# openSX70_ALPHA_V8-20181105-MLF32.net
KiCad netlist of a schematic drawn in EAGLE
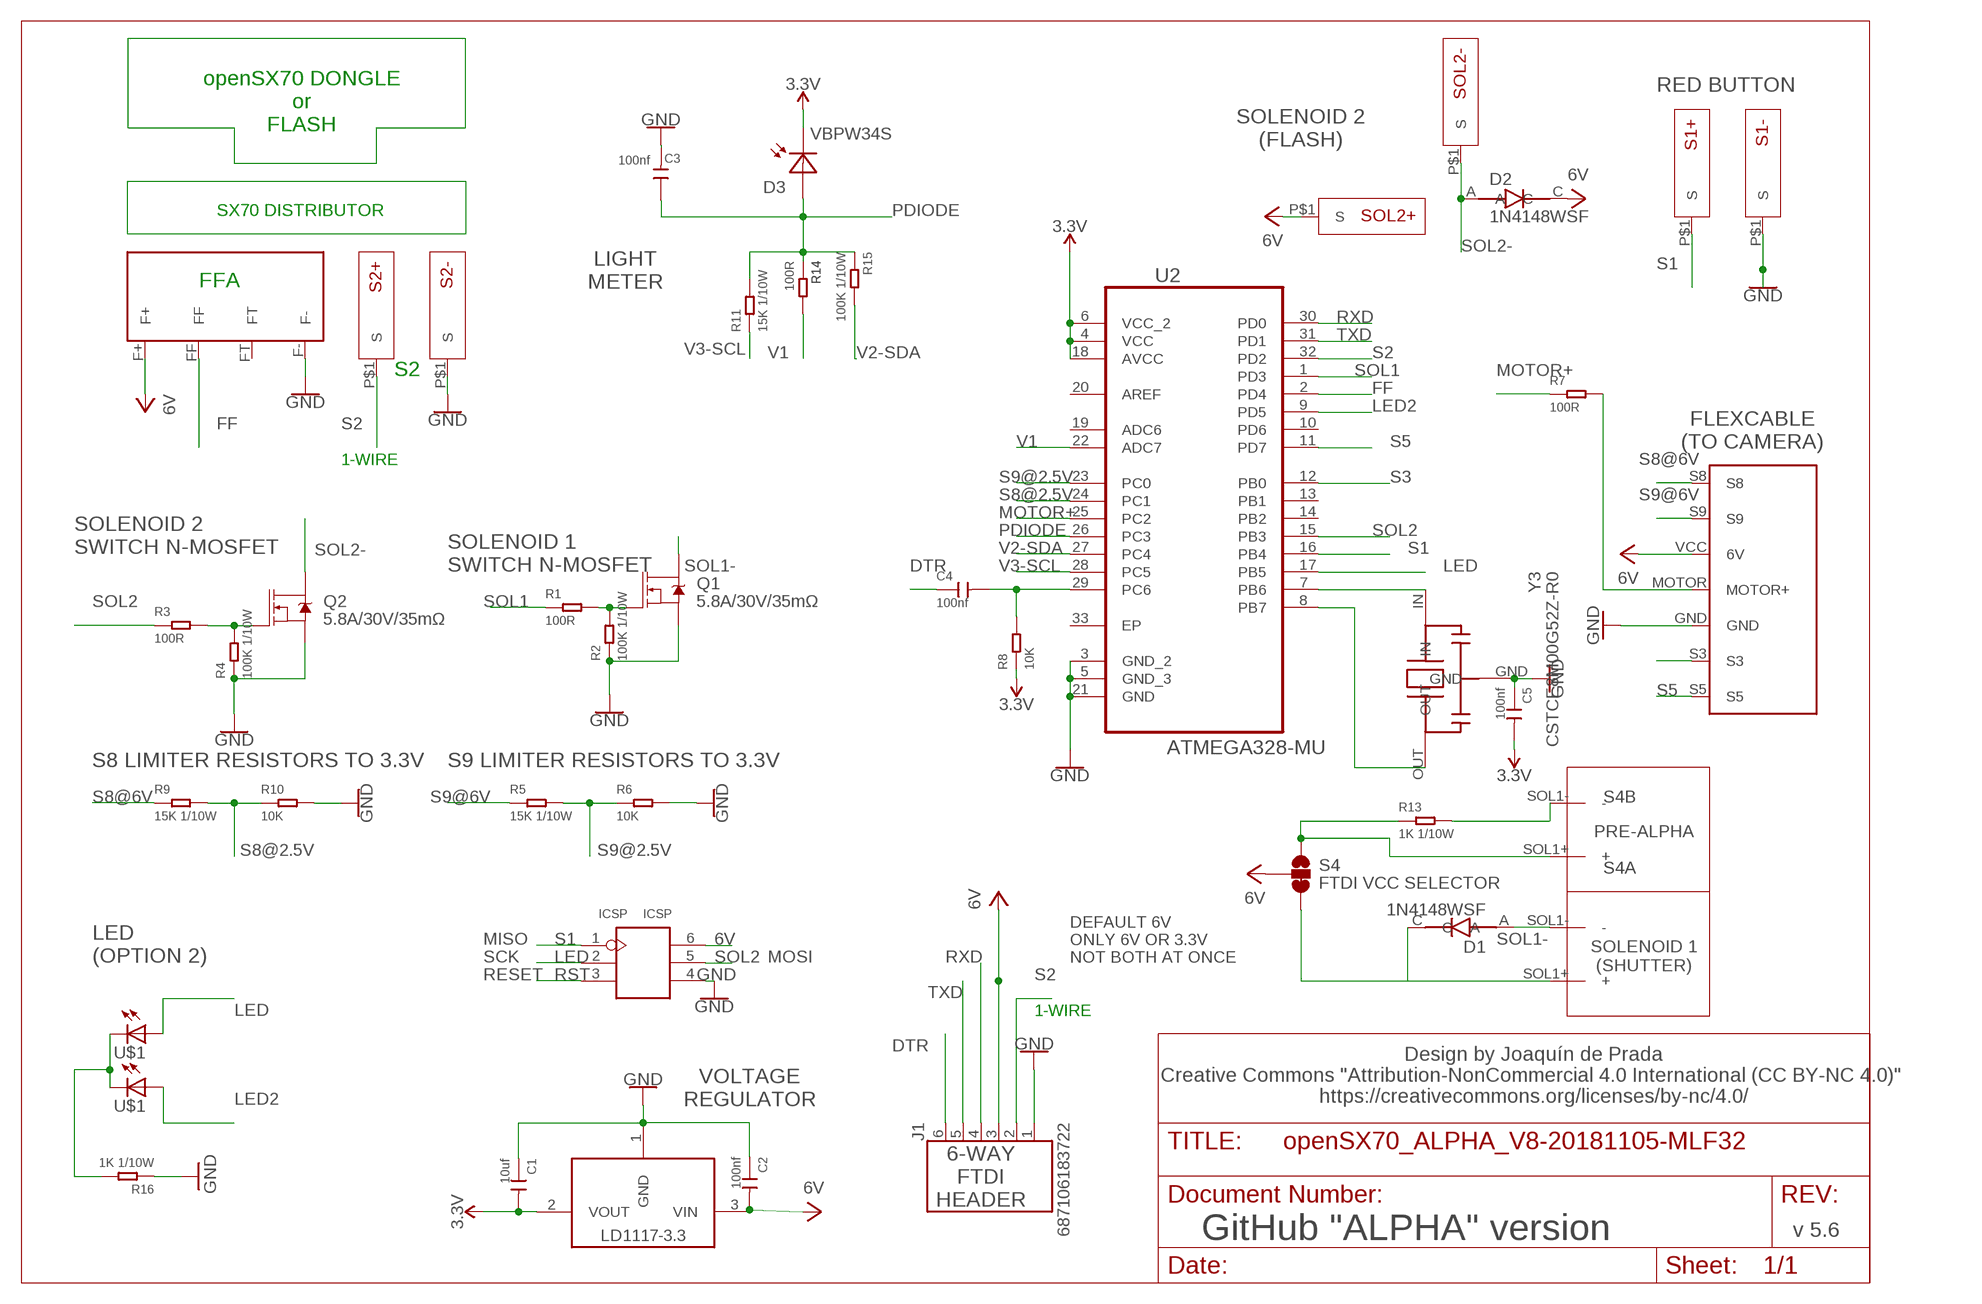
[diagram p0: schematic, sheet 1]

(export (version "E")
  (design (tool "Eeschema 10.0.6"))
  (components
    (comp (ref "C1")
      (value "10uf")
      (footprint "eagle-import:C0603")
      (fields (field (name "MPN") "CC0603KRX5R6BB106"))
      (libsource (lib "eagle-import") (part "CERAMIC-10UF-10V-10%-X5R(0603)"))
    )
    (comp (ref "C2")
      (value "100nf")
      (footprint "eagle-import:C0603")
      (fields (field (name "MPN") "CC0603KRX7R9BB104"))
      (libsource (lib "eagle-import") (part "CERAMIC-100NF-50V-10%-X7R(0603)"))
    )
    (comp (ref "C3")
      (value "100nf")
      (footprint "eagle-import:C0603")
      (fields (field (name "MPN") "CC0603KRX7R9BB104"))
      (libsource (lib "eagle-import") (part "CERAMIC-100NF-50V-10%-X7R(0603)"))
    )
    (comp (ref "C4")
      (value "100nf")
      (footprint "eagle-import:C0603")
      (fields (field (name "MPN") "CC0603KRX7R9BB104"))
      (libsource (lib "eagle-import") (part "CERAMIC-100NF-50V-10%-X7R(0603)"))
    )
    (comp (ref "C5")
      (value "100nf")
      (footprint "eagle-import:C0603")
      (fields (field (name "MPN") "CC0603KRX7R9BB104"))
      (libsource (lib "eagle-import") (part "CERAMIC-100NF-50V-10%-X7R(0603)"))
    )
    (comp (ref "D1")
      (value "1N4148WSF")
      (footprint "eagle-import:SODFL2512X100N")
      (fields (field (name "MANUFACTURER") "Fairchild Semiconductor"))
      (libsource (lib "eagle-import") (part "1N4148WS"))
    )
    (comp (ref "D2")
      (value "1N4148WSF")
      (footprint "eagle-import:SODFL2512X100N")
      (fields (field (name "MANUFACTURER") "Fairchild Semiconductor"))
      (libsource (lib "eagle-import") (part "1N4148WS"))
    )
    (comp (ref "D3")
      (value "VBPW34S")
      (footprint "eagle-import:SOD6439X130N")
      (fields (field (name "DIGI-KEY_PART_NUMBER") "751-1500-1-ND") (field (name "MF") "Vishay"))
      (libsource (lib "eagle-import") (part "VBPW34S"))
    )
    (comp (ref "ICSP")
      (value "ICSP")
      (footprint "eagle-import:H2X3-2.54")
      (libsource (lib "eagle-import") (part "ICSP"))
    )
    (comp (ref "J1")
      (value "687106183722")
      (footprint "eagle-import:687106183722")
      (fields (field (name "MF") "Wurth Electronics"))
      (libsource (lib "eagle-import") (part "687106183722"))
    )
    (comp (ref "LD11172.5V")
      (value "LD1117 2.5V")
      (footprint "eagle-import:SOT223")
      (fields (field (name "MF") "Advanced Monolithic Systems") (field (name "MP") "AMS1117-5.0"))
      (libsource (lib "eagle-import") (part "LD1117-3.3"))
    )
    (comp (ref "Q1")
      (value "5.8A/30V/35mΩ")
      (footprint "eagle-import:SOT23-3")
      (libsource (lib "eagle-import") (part "MOSFET-NCH-AO3404A"))
    )
    (comp (ref "Q2")
      (value "5.8A/30V/35mΩ")
      (footprint "eagle-import:SOT23-3")
      (libsource (lib "eagle-import") (part "MOSFET-NCH-AO3404A"))
    )
    (comp (ref "R1")
      (value "100R")
      (footprint "eagle-import:R0603")
      (fields (field (name "MPN") "RC0603JR-07100RL"))
      (libsource (lib "eagle-import") (part "SMD-RES-100R-5%-1/10W(0603)"))
    )
    (comp (ref "R2")
      (value "100K 1/10W")
      (footprint "eagle-import:R0603")
      (fields (field (name "MPN") "RC0603JR-07100KL"))
      (libsource (lib "eagle-import") (part "SMD-RES-100K-5%-1/10W(0603)"))
    )
    (comp (ref "R3")
      (value "100R")
      (footprint "eagle-import:R0603")
      (fields (field (name "MPN") "RC0603JR-07100RL"))
      (libsource (lib "eagle-import") (part "SMD-RES-100R-5%-1/10W(0603)"))
    )
    (comp (ref "R4")
      (value "100K 1/10W")
      (footprint "eagle-import:R0603")
      (fields (field (name "MPN") "RC0603JR-07100KL"))
      (libsource (lib "eagle-import") (part "SMD-RES-100K-5%-1/10W(0603)"))
    )
    (comp (ref "R5")
      (value "15K 1/10W")
      (footprint "eagle-import:R0603")
      (fields (field (name "MPN") "RC0603FR-0715KL"))
      (libsource (lib "eagle-import") (part "SMD-RES-15K-1%-1/10W(0603)"))
    )
    (comp (ref "R6")
      (value "10K")
      (footprint "eagle-import:R0603")
      (fields (field (name "MPN") "RC0603FR-0710KL"))
      (libsource (lib "eagle-import") (part "SMD-RES-10K-1%-1/10W(0603)"))
    )
    (comp (ref "R7")
      (value "100R")
      (footprint "eagle-import:R0603")
      (fields (field (name "MPN") "RC0603JR-07100RL"))
      (libsource (lib "eagle-import") (part "SMD-RES-100R-5%-1/10W(0603)"))
    )
    (comp (ref "R8")
      (value "10K")
      (footprint "eagle-import:R0603")
      (fields (field (name "MPN") "RC0603FR-0710KL"))
      (libsource (lib "eagle-import") (part "SMD-RES-10K-1%-1/10W(0603)"))
    )
    (comp (ref "R9")
      (value "15K 1/10W")
      (footprint "eagle-import:R0603")
      (fields (field (name "MPN") "RC0603FR-0715KL"))
      (libsource (lib "eagle-import") (part "SMD-RES-15K-1%-1/10W(0603)"))
    )
    (comp (ref "R10")
      (value "10K")
      (footprint "eagle-import:R0603")
      (fields (field (name "MPN") "RC0603FR-0710KL"))
      (libsource (lib "eagle-import") (part "SMD-RES-10K-1%-1/10W(0603)"))
    )
    (comp (ref "R11")
      (value "15K 1/10W")
      (footprint "eagle-import:R0603")
      (fields (field (name "MPN") "RC0603FR-0715KL"))
      (libsource (lib "eagle-import") (part "SMD-RES-15K-1%-1/10W(0603)"))
    )
    (comp (ref "R13")
      (value "1K 1/10W")
      (footprint "eagle-import:R0603")
      (fields (field (name "MPN") "RC0603JR-071KL"))
      (libsource (lib "eagle-import") (part "SMD-RES-1K-5%-1/10W(0603)"))
    )
    (comp (ref "R14")
      (value "100R")
      (footprint "eagle-import:R0603")
      (fields (field (name "MPN") "RC0603JR-07100RL"))
      (libsource (lib "eagle-import") (part "SMD-RES-100R-5%-1/10W(0603)"))
    )
    (comp (ref "R15")
      (value "100K 1/10W")
      (footprint "eagle-import:R0603")
      (fields (field (name "MPN") "RC0603JR-07100KL"))
      (libsource (lib "eagle-import") (part "SMD-RES-100K-5%-1/10W(0603)"))
    )
    (comp (ref "R16")
      (value "1K 1/10W")
      (footprint "eagle-import:R0603")
      (fields (field (name "MPN") "RC0603JR-071KL"))
      (libsource (lib "eagle-import") (part "SMD-RES-1K-5%-1/10W(0603)"))
    )
    (comp (ref "S1+")
      (value "SX70-S-PAD-NEW")
      (footprint "eagle-import:SX70-S-PAD2")
      (libsource (lib "eagle-import") (part "SX70-S-PAD-NEW"))
    )
    (comp (ref "S1-")
      (value "SX70-S-PAD-NEW")
      (footprint "eagle-import:SX70-S-PAD2")
      (libsource (lib "eagle-import") (part "SX70-S-PAD-NEW"))
    )
    (comp (ref "S2+")
      (value "SX70-S-PAD-NEW")
      (footprint "eagle-import:SX70-S-PAD2")
      (libsource (lib "eagle-import") (part "SX70-S-PAD-NEW"))
    )
    (comp (ref "S2-")
      (value "SX70-S-PAD-NEW")
      (footprint "eagle-import:SX70-S-PAD2")
      (libsource (lib "eagle-import") (part "SX70-S-PAD-NEW"))
    )
    (comp (ref "S4")
      (value "FTDI VCC SELECTOR")
      (footprint "eagle-import:SMT-JUMPER_3_1-NC_TRACE_SILK")
      (libsource (lib "eagle-import") (part "JUMPER-SMT_3_1-NC_TRACE_SILK"))
    )
    (comp (ref "SOL1")
      (value "SX70-SOLENOID1-2PADS")
      (footprint "eagle-import:SX70-SOLENOID1-2")
      (libsource (lib "eagle-import") (part "SX70-SOLENOID1-2PADS"))
    )
    (comp (ref "SOL2")
      (value "SX70-SOLENOID1-2PADS")
      (footprint "eagle-import:SX70-SOLENOID1-2")
      (libsource (lib "eagle-import") (part "SX70-SOLENOID1-2PADS"))
    )
    (comp (ref "SOL2+")
      (value "SX70-S-PAD-NEW")
      (footprint "eagle-import:SX70-S-PAD2")
      (libsource (lib "eagle-import") (part "SX70-S-PAD-NEW"))
    )
    (comp (ref "SOL2-")
      (value "SX70-S-PAD-NEW")
      (footprint "eagle-import:SX70-S-PAD2")
      (libsource (lib "eagle-import") (part "SX70-S-PAD-NEW"))
    )
    (comp (ref "U$1")
      (value "DUAL-LED-0603-BIS")
      (footprint "eagle-import:LED_APHB1608SYKSURKC")
      (libsource (lib "eagle-import") (part "DUAL-LED-0603-BIS"))
    )
    (comp (ref "U$2")
      (value "FFA")
      (footprint "eagle-import:FFA-PAD-PACKAGE")
      (libsource (lib "eagle-import") (part "SX70-FFA-PAD"))
    )
    (comp (ref "U$3")
      (value "SX70-7-PAD")
      (footprint "eagle-import:SX70-7-PAD-PROPER")
      (libsource (lib "eagle-import") (part "SX70-7-PAD"))
    )
    (comp (ref "U2")
      (value "ATMEGA328-MU")
      (footprint "eagle-import:QFN50P500X500X100-33N")
      (fields (field (name "MF") "Microchip"))
      (libsource (lib "eagle-import") (part "ATMEGA328-MU"))
    )
    (comp (ref "Y3")
      (value "CSTCE8M00G52Z-R0")
      (footprint "eagle-import:CFP95P160X100-3N")
      (fields (field (name "MF") "Murata") (field (name "MP") "CSTCE16M0V53-R0"))
      (libsource (lib "eagle-import") (part "CSTCE16M0V53-R0"))
    )
  )
  (nets
    (net (code "1") (name "/DTR") (class "Default")
      (node (ref "C4") (pin "1") (pinfunction "1_1") (pintype "passive"))
      (node (ref "J1") (pin "6") (pinfunction "1_6") (pintype "passive"))
    )
    (net (code "2") (name "/FF") (class "Default")
      (node (ref "U$2") (pin "FF") (pinfunction "FF_FF") (pintype "bidirectional"))
      (node (ref "U2") (pin "2") (pinfunction "PD4_2") (pintype "bidirectional"))
    )
    (net (code "3") (name "/LED") (class "Default")
      (node (ref "ICSP") (pin "2") (pinfunction "SCK_2") (pintype "bidirectional"))
      (node (ref "U$1") (pin "1") (pinfunction "A_1") (pintype "passive"))
      (node (ref "U2") (pin "17") (pinfunction "PB5_17") (pintype "bidirectional"))
    )
    (net (code "4") (name "/LED2") (class "Default")
      (node (ref "U$1") (pin "3") (pinfunction "A1_3") (pintype "passive"))
      (node (ref "U2") (pin "9") (pinfunction "PD5_9") (pintype "bidirectional"))
    )
    (net (code "5") (name "/MOTOR+") (class "Default")
      (node (ref "R7") (pin "1") (pinfunction "1_1") (pintype "passive"))
      (node (ref "U2") (pin "25") (pinfunction "PC2_25") (pintype "bidirectional"))
    )
    (net (code "6") (name "/PDIODE") (class "Default")
      (node (ref "C3") (pin "1") (pinfunction "1_1") (pintype "passive"))
      (node (ref "D3") (pin "A") (pinfunction "A_A") (pintype "passive"))
      (node (ref "R11") (pin "2") (pinfunction "2_2") (pintype "passive"))
      (node (ref "R14") (pin "1") (pinfunction "1_1") (pintype "passive"))
      (node (ref "R15") (pin "1") (pinfunction "1_1") (pintype "passive"))
      (node (ref "U2") (pin "26") (pinfunction "PC3_26") (pintype "bidirectional"))
    )
    (net (code "7") (name "/RST") (class "Default")
      (node (ref "ICSP") (pin "3") (pinfunction "RST_3") (pintype "bidirectional"))
    )
    (net (code "8") (name "/RXD") (class "Default")
      (node (ref "J1") (pin "4") (pinfunction "3_4") (pintype "passive"))
      (node (ref "U2") (pin "30") (pinfunction "PD0_30") (pintype "bidirectional"))
    )
    (net (code "9") (name "/S1") (class "Default")
      (node (ref "ICSP") (pin "1") (pinfunction "MISO_1") (pintype "bidirectional"))
      (node (ref "S1+") (pin "P$1") (pinfunction "S_P$1") (pintype "bidirectional"))
      (node (ref "U2") (pin "16") (pinfunction "PB4_16") (pintype "bidirectional"))
    )
    (net (code "10") (name "/S2") (class "Default")
      (node (ref "J1") (pin "2") (pinfunction "5_2") (pintype "passive"))
      (node (ref "S2+") (pin "P$1") (pinfunction "S_P$1") (pintype "bidirectional"))
      (node (ref "U2") (pin "32") (pinfunction "PD2_32") (pintype "bidirectional"))
    )
    (net (code "11") (name "/S3") (class "Default")
      (node (ref "U$3") (pin "S3") (pinfunction "S3_S3") (pintype "bidirectional"))
      (node (ref "U2") (pin "12") (pinfunction "PB0_12") (pintype "bidirectional"))
    )
    (net (code "12") (name "/S5") (class "Default")
      (node (ref "U$3") (pin "S5") (pinfunction "S5_S5") (pintype "bidirectional"))
      (node (ref "U2") (pin "11") (pinfunction "PD7_11") (pintype "bidirectional"))
    )
    (net (code "13") (name "/S8@2.5V") (class "Default")
      (node (ref "R10") (pin "1") (pinfunction "1_1") (pintype "passive"))
      (node (ref "R9") (pin "2") (pinfunction "2_2") (pintype "passive"))
      (node (ref "U2") (pin "24") (pinfunction "PC1_24") (pintype "bidirectional"))
    )
    (net (code "14") (name "/S8@6V") (class "Default")
      (node (ref "R9") (pin "1") (pinfunction "1_1") (pintype "passive"))
      (node (ref "U$3") (pin "S8") (pinfunction "S8_S8") (pintype "bidirectional"))
    )
    (net (code "15") (name "/S9@2.5V") (class "Default")
      (node (ref "R5") (pin "2") (pinfunction "2_2") (pintype "passive"))
      (node (ref "R6") (pin "1") (pinfunction "1_1") (pintype "passive"))
      (node (ref "U2") (pin "23") (pinfunction "PC0_23") (pintype "bidirectional"))
    )
    (net (code "16") (name "/S9@6V") (class "Default")
      (node (ref "R5") (pin "1") (pinfunction "1_1") (pintype "passive"))
      (node (ref "U$3") (pin "S9") (pinfunction "S9_S9") (pintype "bidirectional"))
    )
    (net (code "17") (name "/SOL1") (class "Default")
      (node (ref "R1") (pin "1") (pinfunction "1_1") (pintype "passive"))
      (node (ref "U2") (pin "1") (pinfunction "PD3_1") (pintype "bidirectional"))
    )
    (net (code "18") (name "/SOL1-") (class "Default")
      (node (ref "D1") (pin "A") (pinfunction "A_A") (pintype "passive"))
      (node (ref "Q1") (pin "3") (pinfunction "D_3") (pintype "bidirectional"))
      (node (ref "SOL1") (pin "SOL1-") (pinfunction "-_SOL1-") (pintype "bidirectional"))
    )
    (net (code "19") (name "/SOL2") (class "Default")
      (node (ref "ICSP") (pin "5") (pinfunction "MOSI_5") (pintype "bidirectional"))
      (node (ref "R3") (pin "1") (pinfunction "1_1") (pintype "passive"))
      (node (ref "U2") (pin "15") (pinfunction "PB3_15") (pintype "bidirectional"))
    )
    (net (code "20") (name "/SOL2-") (class "Default")
      (node (ref "D2") (pin "A") (pinfunction "A_A") (pintype "passive"))
      (node (ref "Q2") (pin "3") (pinfunction "D_3") (pintype "bidirectional"))
      (node (ref "SOL2-") (pin "P$1") (pinfunction "S_P$1") (pintype "bidirectional"))
    )
    (net (code "21") (name "/TXD") (class "Default")
      (node (ref "J1") (pin "5") (pinfunction "2_5") (pintype "passive"))
      (node (ref "U2") (pin "31") (pinfunction "PD1_31") (pintype "bidirectional"))
    )
    (net (code "22") (name "/V1") (class "Default")
      (node (ref "R14") (pin "2") (pinfunction "2_2") (pintype "passive"))
      (node (ref "U2") (pin "22") (pinfunction "ADC7_22") (pintype "input"))
    )
    (net (code "23") (name "/V2-SDA") (class "Default")
      (node (ref "R15") (pin "2") (pinfunction "2_2") (pintype "passive"))
      (node (ref "U2") (pin "27") (pinfunction "PC4_27") (pintype "bidirectional"))
    )
    (net (code "24") (name "/V3-SCL") (class "Default")
      (node (ref "R11") (pin "1") (pinfunction "1_1") (pintype "passive"))
      (node (ref "U2") (pin "28") (pinfunction "PC5_28") (pintype "bidirectional"))
    )
    (net (code "25") (name "3.3V") (class "Default")
      (node (ref "C1") (pin "2") (pinfunction "2_2") (pintype "passive"))
      (node (ref "C5") (pin "2") (pinfunction "2_2") (pintype "passive"))
      (node (ref "D3") (pin "C") (pinfunction "C_C") (pintype "passive"))
      (node (ref "LD11172.5V") (pin "2") (pinfunction "VOUT_2") (pintype "bidirectional"))
      (node (ref "R8") (pin "1") (pinfunction "1_1") (pintype "passive"))
      (node (ref "U2") (pin "18") (pinfunction "AVCC_18") (pintype "power_in"))
      (node (ref "U2") (pin "4") (pinfunction "VCC_4") (pintype "power_in"))
      (node (ref "U2") (pin "6") (pinfunction "VCC_2_6") (pintype "power_in"))
    )
    (net (code "26") (name "6V") (class "Default")
      (node (ref "C2") (pin "2") (pinfunction "2_2") (pintype "passive"))
      (node (ref "D2") (pin "C") (pinfunction "C_C") (pintype "passive"))
      (node (ref "ICSP") (pin "6") (pinfunction "VCC_6") (pintype "bidirectional"))
      (node (ref "J1") (pin "3") (pinfunction "4_3") (pintype "passive"))
      (node (ref "LD11172.5V") (pin "3") (pinfunction "VIN_3") (pintype "bidirectional"))
      (node (ref "S4") (pin "2") (pinfunction "2_2") (pintype "passive"))
      (node (ref "SOL2+") (pin "P$1") (pinfunction "S_P$1") (pintype "bidirectional"))
      (node (ref "U$2") (pin "F+") (pinfunction "F+_F+") (pintype "bidirectional"))
      (node (ref "U$3") (pin "VCC") (pinfunction "6V_VCC") (pintype "bidirectional"))
    )
    (net (code "27") (name "GND") (class "Default")
      (node (ref "C1") (pin "1") (pinfunction "1_1") (pintype "passive"))
      (node (ref "C2") (pin "1") (pinfunction "1_1") (pintype "passive"))
      (node (ref "C3") (pin "2") (pinfunction "2_2") (pintype "passive"))
      (node (ref "C5") (pin "1") (pinfunction "1_1") (pintype "passive"))
      (node (ref "ICSP") (pin "4") (pinfunction "GND_4") (pintype "bidirectional"))
      (node (ref "J1") (pin "1") (pinfunction "6_1") (pintype "passive"))
      (node (ref "LD11172.5V") (pin "1") (pinfunction "GND_1") (pintype "bidirectional"))
      (node (ref "Q1") (pin "2") (pinfunction "S_2") (pintype "bidirectional"))
      (node (ref "Q2") (pin "2") (pinfunction "S_2") (pintype "bidirectional"))
      (node (ref "R10") (pin "2") (pinfunction "2_2") (pintype "passive"))
      (node (ref "R16") (pin "1") (pinfunction "1_1") (pintype "passive"))
      (node (ref "R2") (pin "1") (pinfunction "1_1") (pintype "passive"))
      (node (ref "R4") (pin "1") (pinfunction "1_1") (pintype "passive"))
      (node (ref "R6") (pin "2") (pinfunction "2_2") (pintype "passive"))
      (node (ref "S1-") (pin "P$1") (pinfunction "S_P$1") (pintype "bidirectional"))
      (node (ref "S2-") (pin "P$1") (pinfunction "S_P$1") (pintype "bidirectional"))
      (node (ref "U$2") (pin "F-") (pinfunction "F-_F-") (pintype "bidirectional"))
      (node (ref "U$3") (pin "GND") (pinfunction "GND_GND") (pintype "bidirectional"))
      (node (ref "U2") (pin "21") (pinfunction "GND_21") (pintype "passive"))
      (node (ref "U2") (pin "3") (pinfunction "GND_2_3") (pintype "passive"))
      (node (ref "U2") (pin "5") (pinfunction "GND_3_5") (pintype "passive"))
      (node (ref "Y3") (pin "GND") (pinfunction "GND_GND") (pintype "passive"))
    )
    (net (code "28") (name "Net-(Q1-G)") (class "Default")
      (node (ref "Q1") (pin "1") (pinfunction "G_1") (pintype "bidirectional"))
      (node (ref "R1") (pin "2") (pinfunction "2_2") (pintype "passive"))
      (node (ref "R2") (pin "2") (pinfunction "2_2") (pintype "passive"))
    )
    (net (code "29") (name "Net-(Q2-G)") (class "Default")
      (node (ref "Q2") (pin "1") (pinfunction "G_1") (pintype "bidirectional"))
      (node (ref "R3") (pin "2") (pinfunction "2_2") (pintype "passive"))
      (node (ref "R4") (pin "2") (pinfunction "2_2") (pintype "passive"))
    )
    (net (code "30") (name "Net-(SOL1-+)") (class "Default")
      (node (ref "D1") (pin "C") (pinfunction "C_C") (pintype "passive"))
      (node (ref "S4") (pin "3") (pinfunction "3_3") (pintype "passive"))
      (node (ref "SOL1") (pin "SOL1+") (pinfunction "+_SOL1+") (pintype "bidirectional"))
    )
    (net (code "31") (name "Net-(SOL2-+)") (class "Default")
      (node (ref "R13") (pin "1") (pinfunction "1_1") (pintype "passive"))
      (node (ref "S4") (pin "1") (pinfunction "1_1") (pintype "passive"))
      (node (ref "SOL2") (pin "SOL1+") (pinfunction "+_SOL1+") (pintype "bidirectional"))
    )
    (net (code "32") (name "Net-(SOL2--)") (class "Default")
      (node (ref "R13") (pin "2") (pinfunction "2_2") (pintype "passive"))
      (node (ref "SOL2") (pin "SOL1-") (pinfunction "-_SOL1-") (pintype "bidirectional"))
    )
    (net (code "33") (name "Net-(U$1-C)") (class "Default")
      (node (ref "R16") (pin "2") (pinfunction "2_2") (pintype "passive"))
      (node (ref "U$1") (pin "2") (pinfunction "C_2") (pintype "passive"))
      (node (ref "U$1") (pin "4") (pinfunction "C1_4") (pintype "passive"))
    )
    (net (code "34") (name "Net-(U$3-MOTOR+)") (class "Default")
      (node (ref "R7") (pin "2") (pinfunction "2_2") (pintype "passive"))
      (node (ref "U$3") (pin "MOTOR") (pinfunction "MOTOR+_MOTOR") (pintype "bidirectional"))
    )
    (net (code "35") (name "Net-(U2-PB6)") (class "Default")
      (node (ref "U2") (pin "7") (pinfunction "PB6_7") (pintype "bidirectional"))
      (node (ref "Y3") (pin "IN") (pinfunction "IN_IN") (pintype "input"))
    )
    (net (code "36") (name "Net-(U2-PB7)") (class "Default")
      (node (ref "U2") (pin "8") (pinfunction "PB7_8") (pintype "bidirectional"))
      (node (ref "Y3") (pin "OUT") (pinfunction "OUT_OUT") (pintype "output"))
    )
    (net (code "37") (name "Net-(U2-PC6)") (class "Default")
      (node (ref "C4") (pin "2") (pinfunction "2_2") (pintype "passive"))
      (node (ref "R8") (pin "2") (pinfunction "2_2") (pintype "passive"))
      (node (ref "U2") (pin "29") (pinfunction "PC6_29") (pintype "bidirectional"))
    )
    (net (code "38") (name "unconnected-(U$2-PadFT)") (class "Default")
      (node (ref "U$2") (pin "FT") (pinfunction "FT_FT") (pintype "bidirectional"))
    )
    (net (code "39") (name "unconnected-(U2-ADC6-Pad19)") (class "Default")
      (node (ref "U2") (pin "19") (pinfunction "ADC6_19") (pintype "input"))
    )
    (net (code "40") (name "unconnected-(U2-AREF-Pad20)") (class "Default")
      (node (ref "U2") (pin "20") (pinfunction "AREF_20") (pintype "input"))
    )
    (net (code "41") (name "unconnected-(U2-EP-Pad33)") (class "Default")
      (node (ref "U2") (pin "33") (pinfunction "EP_33") (pintype "passive"))
    )
    (net (code "42") (name "unconnected-(U2-PB1-Pad13)") (class "Default")
      (node (ref "U2") (pin "13") (pinfunction "PB1_13") (pintype "bidirectional"))
    )
    (net (code "43") (name "unconnected-(U2-PB2-Pad14)") (class "Default")
      (node (ref "U2") (pin "14") (pinfunction "PB2_14") (pintype "bidirectional"))
    )
    (net (code "44") (name "unconnected-(U2-PD6-Pad10)") (class "Default")
      (node (ref "U2") (pin "10") (pinfunction "PD6_10") (pintype "bidirectional"))
    )
  )
)
